# MCU.net
KiCad netlist of a schematic drawn in Altium Designer
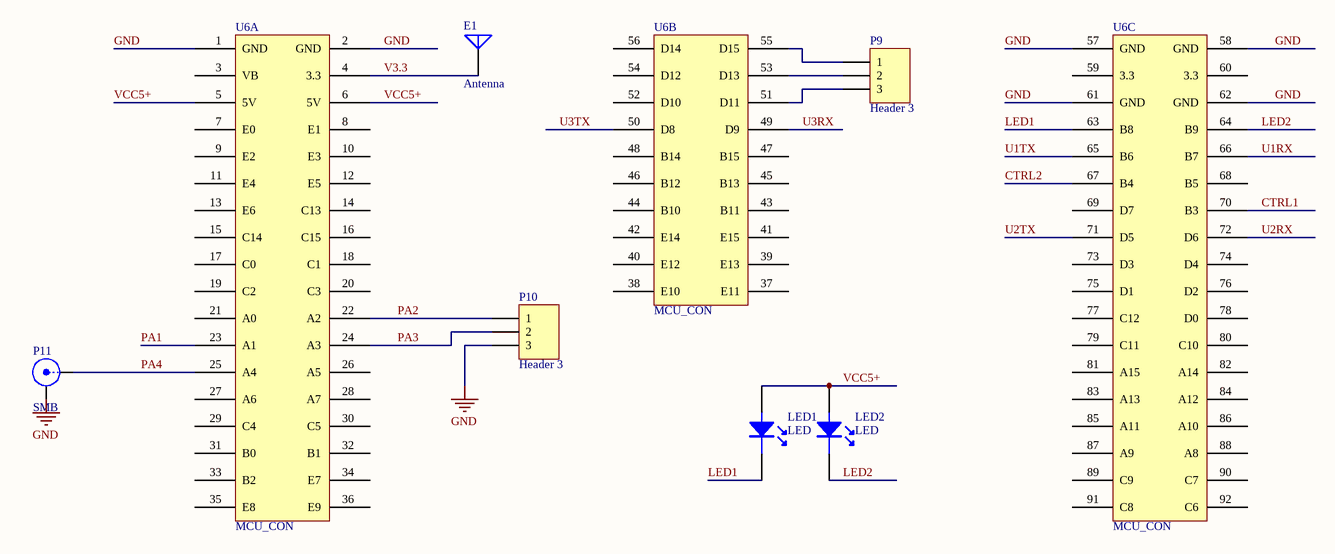
[diagram p0: MCU.SchDoc]

(export (version "E")
  (design (tool "Eeschema 10.0.6"))
  (components
    (comp (ref "E1")
      (value "Antenna")
      (footprint "PIN1")
      (description "Generic Antenna")
      (fields (field (name "PUBLISHER") "Altium Limited"))
      (libsource (lib "Miscellaneous Devices") (part "Antenna"))
    )
    (comp (ref "LED1") (value "LED") (footprint "0805_LED") (libsource (lib "Schlib1") (part "LED")))
    (comp (ref "LED2") (value "LED") (footprint "0805_LED") (libsource (lib "Schlib1") (part "LED")))
    (comp (ref "P9")
      (value "Header 3")
      (footprint "HDR1X3")
      (description "Header, 3-Pin")
      (fields (field (name "PUBLISHER") "Altium Limited"))
      (libsource (lib "Miscellaneous Connectors") (part "Header 3"))
    )
    (comp (ref "P10")
      (value "Header 3")
      (footprint "HDR1X3")
      (description "Header, 3-Pin")
      (fields (field (name "PUBLISHER") "Altium Limited"))
      (libsource (lib "Miscellaneous Connectors") (part "Header 3"))
    )
    (comp (ref "P11")
      (value "SMB")
      (footprint "SMB_V-RJ45")
      (description "SMB Straight Connector")
      (fields (field (name "PUBLISHER") "Altium Limited"))
      (libsource (lib "Miscellaneous Connectors") (part "SMB"))
    )
    (comp (ref "U6") (value "MCU_CON") (footprint "MCU_CON") (libsource (lib "Schlib1") (part "MCU_CON")))
  )
  (nets
    (net (code "1") (name "/CTRL1") (class "Default")
      (node (ref "U6") (pin "70") (pinfunction "B3_70") (pintype "passive"))
    )
    (net (code "2") (name "/CTRL2") (class "Default")
      (node (ref "U6") (pin "67") (pinfunction "B4_67") (pintype "passive"))
    )
    (net (code "3") (name "/LED1") (class "Default")
      (node (ref "LED1") (pin "2") (pinfunction "K_2") (pintype "passive"))
      (node (ref "U6") (pin "63") (pinfunction "B8_63") (pintype "passive"))
    )
    (net (code "4") (name "/LED2") (class "Default")
      (node (ref "LED2") (pin "2") (pinfunction "K_2") (pintype "passive"))
      (node (ref "U6") (pin "64") (pinfunction "B9_64") (pintype "passive"))
    )
    (net (code "5") (name "/PA1") (class "Default")
      (node (ref "U6") (pin "23") (pinfunction "A1_23") (pintype "passive"))
    )
    (net (code "6") (name "/PA2") (class "Default")
      (node (ref "P10") (pin "1") (pinfunction "1_1") (pintype "passive"))
      (node (ref "U6") (pin "22") (pinfunction "A2_22") (pintype "passive"))
    )
    (net (code "7") (name "/PA3") (class "Default")
      (node (ref "P10") (pin "2") (pinfunction "2_2") (pintype "passive"))
      (node (ref "U6") (pin "24") (pinfunction "A3_24") (pintype "passive"))
    )
    (net (code "8") (name "/PA4") (class "Default")
      (node (ref "P11") (pin "1") (pinfunction "X_1") (pintype "passive"))
      (node (ref "U6") (pin "25") (pinfunction "A4_25") (pintype "passive"))
    )
    (net (code "9") (name "/U1RX") (class "Default")
      (node (ref "U6") (pin "66") (pinfunction "B7_66") (pintype "passive"))
    )
    (net (code "10") (name "/U1TX") (class "Default")
      (node (ref "U6") (pin "65") (pinfunction "B6_65") (pintype "passive"))
    )
    (net (code "11") (name "/U2RX") (class "Default")
      (node (ref "U6") (pin "72") (pinfunction "D6_72") (pintype "passive"))
    )
    (net (code "12") (name "/U2TX") (class "Default")
      (node (ref "U6") (pin "71") (pinfunction "D5_71") (pintype "passive"))
    )
    (net (code "13") (name "/U3RX") (class "Default")
      (node (ref "U6") (pin "49") (pinfunction "D9_49") (pintype "passive"))
    )
    (net (code "14") (name "/U3TX") (class "Default")
      (node (ref "U6") (pin "50") (pinfunction "D8_50") (pintype "passive"))
    )
    (net (code "15") (name "/V3.3") (class "Default")
      (node (ref "E1") (pin "1") (pinfunction "A_1") (pintype "passive"))
      (node (ref "U6") (pin "4") (pinfunction "3.3_4") (pintype "passive"))
    )
    (net (code "16") (name "/VCC5+") (class "Default")
      (node (ref "LED1") (pin "1") (pinfunction "A_1") (pintype "passive"))
      (node (ref "LED2") (pin "1") (pinfunction "A_1") (pintype "passive"))
      (node (ref "U6") (pin "5") (pinfunction "5V_5") (pintype "passive"))
      (node (ref "U6") (pin "6") (pinfunction "5V_6") (pintype "passive"))
    )
    (net (code "17") (name "GND") (class "Default")
      (node (ref "P10") (pin "3") (pinfunction "3_3") (pintype "passive"))
      (node (ref "P11") (pin "2") (pinfunction "Y_2") (pintype "passive"))
      (node (ref "U6") (pin "1") (pinfunction "GND_1") (pintype "passive"))
      (node (ref "U6") (pin "2") (pinfunction "GND_2") (pintype "passive"))
      (node (ref "U6") (pin "57") (pinfunction "GND_57") (pintype "passive"))
      (node (ref "U6") (pin "58") (pinfunction "GND_58") (pintype "passive"))
      (node (ref "U6") (pin "61") (pinfunction "GND_61") (pintype "passive"))
      (node (ref "U6") (pin "62") (pinfunction "GND_62") (pintype "passive"))
    )
    (net (code "18") (name "Net-(U6B-D11)") (class "Default")
      (node (ref "P9") (pin "3") (pinfunction "3_3") (pintype "passive"))
      (node (ref "U6") (pin "51") (pinfunction "D11_51") (pintype "passive"))
    )
    (net (code "19") (name "Net-(U6B-D13)") (class "Default")
      (node (ref "P9") (pin "2") (pinfunction "2_2") (pintype "passive"))
      (node (ref "U6") (pin "53") (pinfunction "D13_53") (pintype "passive"))
    )
    (net (code "20") (name "Net-(U6B-D15)") (class "Default")
      (node (ref "P9") (pin "1") (pinfunction "1_1") (pintype "passive"))
      (node (ref "U6") (pin "55") (pinfunction "D15_55") (pintype "passive"))
    )
    (net (code "21") (name "unconnected-(U6A-A0-Pad21)") (class "Default")
      (node (ref "U6") (pin "21") (pinfunction "A0_21") (pintype "passive"))
    )
    (net (code "22") (name "unconnected-(U6A-A5-Pad26)") (class "Default")
      (node (ref "U6") (pin "26") (pinfunction "A5_26") (pintype "passive"))
    )
    (net (code "23") (name "unconnected-(U6A-A6-Pad27)") (class "Default")
      (node (ref "U6") (pin "27") (pinfunction "A6_27") (pintype "passive"))
    )
    (net (code "24") (name "unconnected-(U6A-A7-Pad28)") (class "Default")
      (node (ref "U6") (pin "28") (pinfunction "A7_28") (pintype "passive"))
    )
    (net (code "25") (name "unconnected-(U6A-B0-Pad31)") (class "Default")
      (node (ref "U6") (pin "31") (pinfunction "B0_31") (pintype "passive"))
    )
    (net (code "26") (name "unconnected-(U6A-B1-Pad32)") (class "Default")
      (node (ref "U6") (pin "32") (pinfunction "B1_32") (pintype "passive"))
    )
    (net (code "27") (name "unconnected-(U6A-B2-Pad33)") (class "Default")
      (node (ref "U6") (pin "33") (pinfunction "B2_33") (pintype "passive"))
    )
    (net (code "28") (name "unconnected-(U6A-C0-Pad17)") (class "Default")
      (node (ref "U6") (pin "17") (pinfunction "C0_17") (pintype "passive"))
    )
    (net (code "29") (name "unconnected-(U6A-C1-Pad18)") (class "Default")
      (node (ref "U6") (pin "18") (pinfunction "C1_18") (pintype "passive"))
    )
    (net (code "30") (name "unconnected-(U6A-C2-Pad19)") (class "Default")
      (node (ref "U6") (pin "19") (pinfunction "C2_19") (pintype "passive"))
    )
    (net (code "31") (name "unconnected-(U6A-C3-Pad20)") (class "Default")
      (node (ref "U6") (pin "20") (pinfunction "C3_20") (pintype "passive"))
    )
    (net (code "32") (name "unconnected-(U6A-C4-Pad29)") (class "Default")
      (node (ref "U6") (pin "29") (pinfunction "C4_29") (pintype "passive"))
    )
    (net (code "33") (name "unconnected-(U6A-C5-Pad30)") (class "Default")
      (node (ref "U6") (pin "30") (pinfunction "C5_30") (pintype "passive"))
    )
    (net (code "34") (name "unconnected-(U6A-C13-Pad14)") (class "Default")
      (node (ref "U6") (pin "14") (pinfunction "C13_14") (pintype "passive"))
    )
    (net (code "35") (name "unconnected-(U6A-C14-Pad15)") (class "Default")
      (node (ref "U6") (pin "15") (pinfunction "C14_15") (pintype "passive"))
    )
    (net (code "36") (name "unconnected-(U6A-C15-Pad16)") (class "Default")
      (node (ref "U6") (pin "16") (pinfunction "C15_16") (pintype "passive"))
    )
    (net (code "37") (name "unconnected-(U6A-E0-Pad7)") (class "Default")
      (node (ref "U6") (pin "7") (pinfunction "E0_7") (pintype "passive"))
    )
    (net (code "38") (name "unconnected-(U6A-E1-Pad8)") (class "Default")
      (node (ref "U6") (pin "8") (pinfunction "E1_8") (pintype "passive"))
    )
    (net (code "39") (name "unconnected-(U6A-E2-Pad9)") (class "Default")
      (node (ref "U6") (pin "9") (pinfunction "E2_9") (pintype "passive"))
    )
    (net (code "40") (name "unconnected-(U6A-E3-Pad10)") (class "Default")
      (node (ref "U6") (pin "10") (pinfunction "E3_10") (pintype "passive"))
    )
    (net (code "41") (name "unconnected-(U6A-E4-Pad11)") (class "Default")
      (node (ref "U6") (pin "11") (pinfunction "E4_11") (pintype "passive"))
    )
    (net (code "42") (name "unconnected-(U6A-E5-Pad12)") (class "Default")
      (node (ref "U6") (pin "12") (pinfunction "E5_12") (pintype "passive"))
    )
    (net (code "43") (name "unconnected-(U6A-E6-Pad13)") (class "Default")
      (node (ref "U6") (pin "13") (pinfunction "E6_13") (pintype "passive"))
    )
    (net (code "44") (name "unconnected-(U6A-E7-Pad34)") (class "Default")
      (node (ref "U6") (pin "34") (pinfunction "E7_34") (pintype "passive"))
    )
    (net (code "45") (name "unconnected-(U6A-E8-Pad35)") (class "Default")
      (node (ref "U6") (pin "35") (pinfunction "E8_35") (pintype "passive"))
    )
    (net (code "46") (name "unconnected-(U6A-E9-Pad36)") (class "Default")
      (node (ref "U6") (pin "36") (pinfunction "E9_36") (pintype "passive"))
    )
    (net (code "47") (name "unconnected-(U6A-VB-Pad3)") (class "Default")
      (node (ref "U6") (pin "3") (pinfunction "VB_3") (pintype "passive"))
    )
    (net (code "48") (name "unconnected-(U6B-B10-Pad44)") (class "Default")
      (node (ref "U6") (pin "44") (pinfunction "B10_44") (pintype "passive"))
    )
    (net (code "49") (name "unconnected-(U6B-B11-Pad43)") (class "Default")
      (node (ref "U6") (pin "43") (pinfunction "B11_43") (pintype "passive"))
    )
    (net (code "50") (name "unconnected-(U6B-B12-Pad46)") (class "Default")
      (node (ref "U6") (pin "46") (pinfunction "B12_46") (pintype "passive"))
    )
    (net (code "51") (name "unconnected-(U6B-B13-Pad45)") (class "Default")
      (node (ref "U6") (pin "45") (pinfunction "B13_45") (pintype "passive"))
    )
    (net (code "52") (name "unconnected-(U6B-B14-Pad48)") (class "Default")
      (node (ref "U6") (pin "48") (pinfunction "B14_48") (pintype "passive"))
    )
    (net (code "53") (name "unconnected-(U6B-B15-Pad47)") (class "Default")
      (node (ref "U6") (pin "47") (pinfunction "B15_47") (pintype "passive"))
    )
    (net (code "54") (name "unconnected-(U6B-D10-Pad52)") (class "Default")
      (node (ref "U6") (pin "52") (pinfunction "D10_52") (pintype "passive"))
    )
    (net (code "55") (name "unconnected-(U6B-D12-Pad54)") (class "Default")
      (node (ref "U6") (pin "54") (pinfunction "D12_54") (pintype "passive"))
    )
    (net (code "56") (name "unconnected-(U6B-D14-Pad56)") (class "Default")
      (node (ref "U6") (pin "56") (pinfunction "D14_56") (pintype "passive"))
    )
    (net (code "57") (name "unconnected-(U6B-E10-Pad38)") (class "Default")
      (node (ref "U6") (pin "38") (pinfunction "E10_38") (pintype "passive"))
    )
    (net (code "58") (name "unconnected-(U6B-E11-Pad37)") (class "Default")
      (node (ref "U6") (pin "37") (pinfunction "E11_37") (pintype "passive"))
    )
    (net (code "59") (name "unconnected-(U6B-E12-Pad40)") (class "Default")
      (node (ref "U6") (pin "40") (pinfunction "E12_40") (pintype "passive"))
    )
    (net (code "60") (name "unconnected-(U6B-E13-Pad39)") (class "Default")
      (node (ref "U6") (pin "39") (pinfunction "E13_39") (pintype "passive"))
    )
    (net (code "61") (name "unconnected-(U6B-E14-Pad42)") (class "Default")
      (node (ref "U6") (pin "42") (pinfunction "E14_42") (pintype "passive"))
    )
    (net (code "62") (name "unconnected-(U6B-E15-Pad41)") (class "Default")
      (node (ref "U6") (pin "41") (pinfunction "E15_41") (pintype "passive"))
    )
    (net (code "63") (name "unconnected-(U6C-3.3-Pad59)") (class "Default")
      (node (ref "U6") (pin "59") (pinfunction "3.3_59") (pintype "passive"))
    )
    (net (code "64") (name "unconnected-(U6C-3.3-Pad60)") (class "Default")
      (node (ref "U6") (pin "60") (pinfunction "3.3_60") (pintype "passive"))
    )
    (net (code "65") (name "unconnected-(U6C-A8-Pad88)") (class "Default")
      (node (ref "U6") (pin "88") (pinfunction "A8_88") (pintype "passive"))
    )
    (net (code "66") (name "unconnected-(U6C-A9-Pad87)") (class "Default")
      (node (ref "U6") (pin "87") (pinfunction "A9_87") (pintype "passive"))
    )
    (net (code "67") (name "unconnected-(U6C-A10-Pad86)") (class "Default")
      (node (ref "U6") (pin "86") (pinfunction "A10_86") (pintype "passive"))
    )
    (net (code "68") (name "unconnected-(U6C-A11-Pad85)") (class "Default")
      (node (ref "U6") (pin "85") (pinfunction "A11_85") (pintype "passive"))
    )
    (net (code "69") (name "unconnected-(U6C-A12-Pad84)") (class "Default")
      (node (ref "U6") (pin "84") (pinfunction "A12_84") (pintype "passive"))
    )
    (net (code "70") (name "unconnected-(U6C-A13-Pad83)") (class "Default")
      (node (ref "U6") (pin "83") (pinfunction "A13_83") (pintype "passive"))
    )
    (net (code "71") (name "unconnected-(U6C-A14-Pad82)") (class "Default")
      (node (ref "U6") (pin "82") (pinfunction "A14_82") (pintype "passive"))
    )
    (net (code "72") (name "unconnected-(U6C-A15-Pad81)") (class "Default")
      (node (ref "U6") (pin "81") (pinfunction "A15_81") (pintype "passive"))
    )
    (net (code "73") (name "unconnected-(U6C-B5-Pad68)") (class "Default")
      (node (ref "U6") (pin "68") (pinfunction "B5_68") (pintype "passive"))
    )
    (net (code "74") (name "unconnected-(U6C-C6-Pad92)") (class "Default")
      (node (ref "U6") (pin "92") (pinfunction "C6_92") (pintype "passive"))
    )
    (net (code "75") (name "unconnected-(U6C-C7-Pad90)") (class "Default")
      (node (ref "U6") (pin "90") (pinfunction "C7_90") (pintype "passive"))
    )
    (net (code "76") (name "unconnected-(U6C-C8-Pad91)") (class "Default")
      (node (ref "U6") (pin "91") (pinfunction "C8_91") (pintype "passive"))
    )
    (net (code "77") (name "unconnected-(U6C-C9-Pad89)") (class "Default")
      (node (ref "U6") (pin "89") (pinfunction "C9_89") (pintype "passive"))
    )
    (net (code "78") (name "unconnected-(U6C-C10-Pad80)") (class "Default")
      (node (ref "U6") (pin "80") (pinfunction "C10_80") (pintype "passive"))
    )
    (net (code "79") (name "unconnected-(U6C-C11-Pad79)") (class "Default")
      (node (ref "U6") (pin "79") (pinfunction "C11_79") (pintype "passive"))
    )
    (net (code "80") (name "unconnected-(U6C-C12-Pad77)") (class "Default")
      (node (ref "U6") (pin "77") (pinfunction "C12_77") (pintype "passive"))
    )
    (net (code "81") (name "unconnected-(U6C-D0-Pad78)") (class "Default")
      (node (ref "U6") (pin "78") (pinfunction "D0_78") (pintype "passive"))
    )
    (net (code "82") (name "unconnected-(U6C-D1-Pad75)") (class "Default")
      (node (ref "U6") (pin "75") (pinfunction "D1_75") (pintype "passive"))
    )
    (net (code "83") (name "unconnected-(U6C-D2-Pad76)") (class "Default")
      (node (ref "U6") (pin "76") (pinfunction "D2_76") (pintype "passive"))
    )
    (net (code "84") (name "unconnected-(U6C-D3-Pad73)") (class "Default")
      (node (ref "U6") (pin "73") (pinfunction "D3_73") (pintype "passive"))
    )
    (net (code "85") (name "unconnected-(U6C-D4-Pad74)") (class "Default")
      (node (ref "U6") (pin "74") (pinfunction "D4_74") (pintype "passive"))
    )
    (net (code "86") (name "unconnected-(U6C-D7-Pad69)") (class "Default")
      (node (ref "U6") (pin "69") (pinfunction "D7_69") (pintype "passive"))
    )
  )
)
